# untitled-1_0.net
KiCad netlist of a schematic drawn in EAGLE
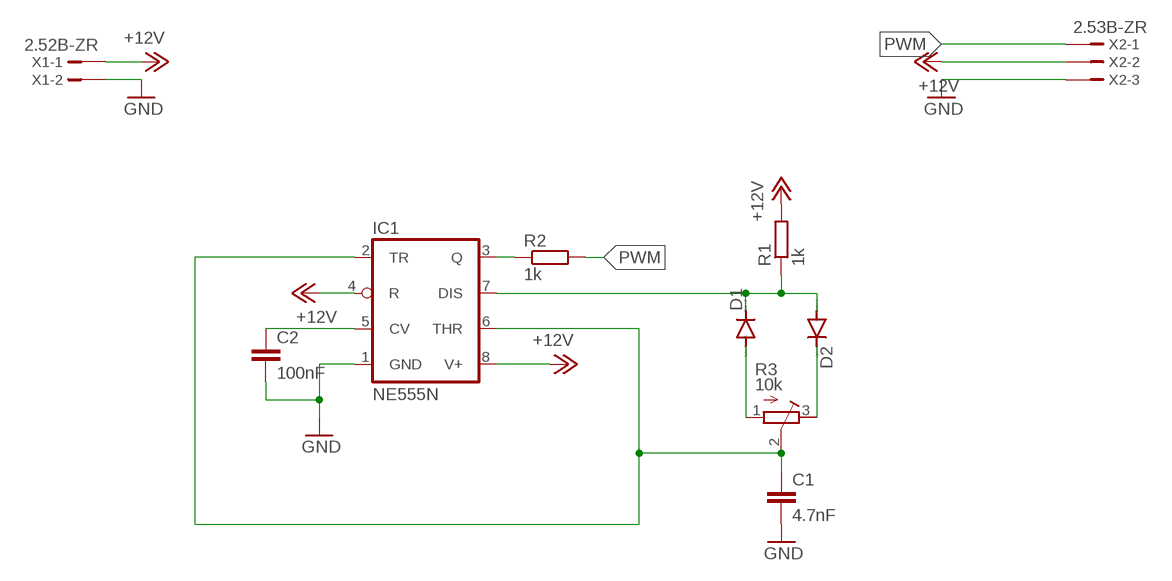
[diagram p0: schematic, sheet 1]

(export (version "E")
  (design (tool "Eeschema 10.0.6"))
  (components
    (comp (ref "C1")
      (value "4.7nF")
      (footprint "eagle-import:C050-030X075")
      (libsource (lib "eagle-import") (part "C-EU050-030X075"))
    )
    (comp (ref "C2")
      (value "100nF")
      (footprint "eagle-import:C025-025X050")
      (libsource (lib "eagle-import") (part "C-EU025-025X050"))
    )
    (comp (ref "D1")
      (value "1N40045")
      (footprint "eagle-import:DO41-5")
      (libsource (lib "eagle-import") (part "1N40045"))
    )
    (comp (ref "D2")
      (value "1N40045")
      (footprint "eagle-import:DO41-5")
      (libsource (lib "eagle-import") (part "1N40045"))
    )
    (comp (ref "IC1")
      (value "NE555N")
      (footprint "eagle-import:DIL08")
      (libsource (lib "eagle-import") (part "555NNE"))
    )
    (comp (ref "R1")
      (value "1k")
      (footprint "eagle-import:0204_7")
      (libsource (lib "eagle-import") (part "R-EU_0204/7"))
    )
    (comp (ref "R2")
      (value "1k")
      (footprint "eagle-import:0204_7")
      (libsource (lib "eagle-import") (part "R-EU_0204/7"))
    )
    (comp (ref "R3")
      (value "10k")
      (footprint "eagle-import:RTRIM3296W")
      (libsource (lib "eagle-import") (part "R-TRIMM3296W"))
    )
    (comp (ref "X1")
      (value "2.52B-ZR")
      (footprint "eagle-import:B2B-ZR2.5")
      (libsource (lib "eagle-import") (part "?2B-ZR2.5"))
    )
    (comp (ref "X2")
      (value "2.53B-ZR")
      (footprint "eagle-import:B3B-ZR2.5")
      (libsource (lib "eagle-import") (part "?3B-ZR2.5"))
    )
  )
  (nets
    (net (code "1") (name "+12V") (class "Default")
      (node (ref "IC1") (pin "4") (pinfunction "R_4") (pintype "input"))
      (node (ref "IC1") (pin "8") (pinfunction "V+_8") (pintype "power_in"))
      (node (ref "R1") (pin "2") (pinfunction "2_2") (pintype "passive"))
      (node (ref "X1") (pin "1") (pinfunction "1_1") (pintype "passive"))
      (node (ref "X2") (pin "2") (pinfunction "1_2") (pintype "passive"))
    )
    (net (code "2") (name "GND") (class "Default")
      (node (ref "C1") (pin "2") (pinfunction "2_2") (pintype "passive"))
      (node (ref "C2") (pin "2") (pinfunction "2_2") (pintype "passive"))
      (node (ref "IC1") (pin "1") (pinfunction "GND_1") (pintype "power_in"))
      (node (ref "X1") (pin "2") (pinfunction "1_2") (pintype "passive"))
      (node (ref "X2") (pin "3") (pinfunction "1_3") (pintype "passive"))
    )
    (net (code "3") (name "Net-(IC1-CV)") (class "Default")
      (node (ref "C2") (pin "1") (pinfunction "1_1") (pintype "passive"))
      (node (ref "IC1") (pin "5") (pinfunction "CV_5") (pintype "input"))
    )
    (net (code "4") (name "Net-(IC1-DIS)") (class "Default")
      (node (ref "D1") (pin "C") (pinfunction "C_C") (pintype "passive"))
      (node (ref "D2") (pin "A") (pinfunction "A_A") (pintype "passive"))
      (node (ref "IC1") (pin "7") (pinfunction "DIS_7") (pintype "input"))
      (node (ref "R1") (pin "1") (pinfunction "1_1") (pintype "passive"))
    )
    (net (code "5") (name "Net-(IC1-Q)") (class "Default")
      (node (ref "IC1") (pin "3") (pinfunction "Q_3") (pintype "output"))
      (node (ref "R2") (pin "1") (pinfunction "1_1") (pintype "passive"))
    )
    (net (code "6") (name "Net-(IC1-THR)") (class "Default")
      (node (ref "C1") (pin "1") (pinfunction "1_1") (pintype "passive"))
      (node (ref "IC1") (pin "2") (pinfunction "TR_2") (pintype "input"))
      (node (ref "IC1") (pin "6") (pinfunction "THR_6") (pintype "input"))
      (node (ref "R3") (pin "2") (pinfunction "S_2") (pintype "passive"))
    )
    (net (code "7") (name "Net-(R3-A)") (class "Default")
      (node (ref "D1") (pin "A") (pinfunction "A_A") (pintype "passive"))
      (node (ref "R3") (pin "1") (pinfunction "A_1") (pintype "passive"))
    )
    (net (code "8") (name "Net-(R3-E)") (class "Default")
      (node (ref "D2") (pin "C") (pinfunction "C_C") (pintype "passive"))
      (node (ref "R3") (pin "3") (pinfunction "E_3") (pintype "passive"))
    )
    (net (code "9") (name "PWM") (class "Default")
      (node (ref "R2") (pin "2") (pinfunction "2_2") (pintype "passive"))
      (node (ref "X2") (pin "1") (pinfunction "1_1") (pintype "passive"))
    )
  )
)
